# Sensor_Schematic.net
KiCad netlist of a schematic drawn in Altium Designer
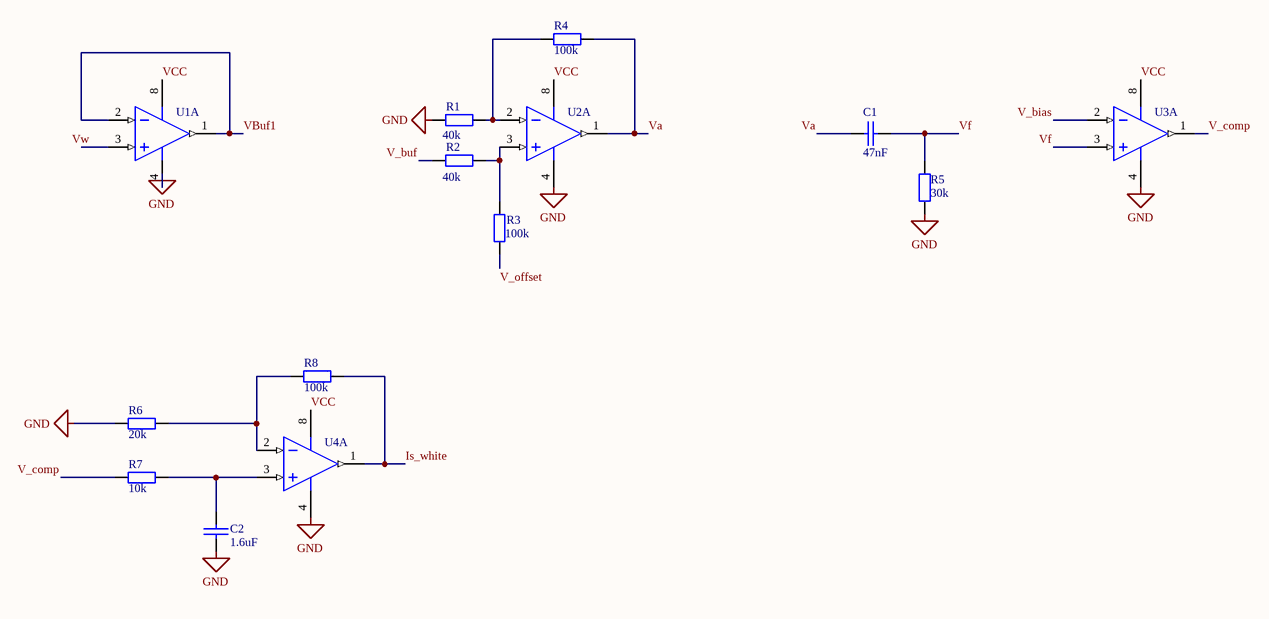
[diagram p0: Sensor Schematic.SchDoc]

(export (version "E")
  (design (tool "Eeschema 10.0.6"))
  (components
    (comp (ref "C1")
      (value "47nF")
      (footprint "0805 CAP")
      (description "SMT ceramic capacitor 0805 size")
      (libsource (lib "EE209_Library") (part "CerCap_SMT_0805"))
    )
    (comp (ref "C2")
      (value "1.6uF")
      (footprint "0805 CAP")
      (description "SMT ceramic capacitor 0805 size")
      (libsource (lib "EE209_Library") (part "CerCap_SMT_0805"))
    )
    (comp (ref "R1")
      (value "40k")
      (footprint "0805 RES")
      (description "0805 resistor")
      (fields (field (name "PUBLISHER") "Altium Limited"))
      (libsource (lib "") (part "Res_SMT_0805_1"))
    )
    (comp (ref "R2")
      (value "40k")
      (footprint "0805 RES")
      (description "0805 resistor")
      (fields (field (name "PUBLISHER") "Altium Limited"))
      (libsource (lib "") (part "Res_SMT_0805_1"))
    )
    (comp (ref "R3")
      (value "100k")
      (footprint "0805 RES")
      (description "0805 resistor")
      (fields (field (name "PUBLISHER") "Altium Limited"))
      (libsource (lib "") (part "Res_SMT_0805_2"))
    )
    (comp (ref "R4")
      (value "100k")
      (footprint "0805 RES")
      (description "0805 resistor")
      (fields (field (name "PUBLISHER") "Altium Limited"))
      (libsource (lib "EE209_Library") (part "Res_SMT_0805"))
    )
    (comp (ref "R5")
      (value "30k")
      (footprint "0805 RES")
      (description "0805 resistor")
      (fields (field (name "PUBLISHER") "Altium Limited"))
      (libsource (lib "") (part "Res_SMT_0805_2"))
    )
    (comp (ref "R6")
      (value "20k")
      (footprint "0805 RES")
      (description "0805 resistor")
      (fields (field (name "PUBLISHER") "Altium Limited"))
      (libsource (lib "EE209_Library") (part "Res_SMT_0805"))
    )
    (comp (ref "R7")
      (value "10k")
      (footprint "0805 RES")
      (description "0805 resistor")
      (fields (field (name "PUBLISHER") "Altium Limited"))
      (libsource (lib "EE209_Library") (part "Res_SMT_0805"))
    )
    (comp (ref "R8")
      (value "100k")
      (footprint "0805 RES")
      (description "0805 resistor")
      (fields (field (name "PUBLISHER") "Altium Limited"))
      (libsource (lib "EE209_Library") (part "Res_SMT_0805"))
    )
    (comp (ref "U1")
      (value "~")
      (footprint "SO - 8")
      (description "IC OPAMP GP 10MHZ 8SOIC")
      (fields
        (field (name "MANUFACTURER") "Texas Instruments")
        (field (name "MANUFACTURER PART NUMBER") "TLC082CDR")
      )
      (libsource (lib "EE209_Library") (part "TLC082_SMT_SOIC8"))
    )
    (comp (ref "U2")
      (value "~")
      (footprint "SO - 8")
      (description "IC OPAMP GP 10MHZ 8SOIC")
      (fields
        (field (name "MANUFACTURER") "Texas Instruments")
        (field (name "MANUFACTURER PART NUMBER") "TLC082CDR")
      )
      (libsource (lib "EE209_Library") (part "TLC082_SMT_SOIC8"))
    )
    (comp (ref "U3")
      (value "~")
      (footprint "SO - 8")
      (description "IC OPAMP GP 10MHZ 8SOIC")
      (fields
        (field (name "MANUFACTURER") "Texas Instruments")
        (field (name "MANUFACTURER PART NUMBER") "TLC082CDR")
      )
      (libsource (lib "EE209_Library") (part "TLC082_SMT_SOIC8"))
    )
    (comp (ref "U4")
      (value "~")
      (footprint "SO - 8")
      (description "IC OPAMP GP 10MHZ 8SOIC")
      (fields
        (field (name "MANUFACTURER") "Texas Instruments")
        (field (name "MANUFACTURER PART NUMBER") "TLC082CDR")
      )
      (libsource (lib "EE209_Library") (part "TLC082_SMT_SOIC8"))
    )
  )
  (nets
    (net (code "1") (name "/Is_white") (class "Default")
      (node (ref "R8") (pin "1") (pinfunction "1_1") (pintype "passive"))
      (node (ref "U4") (pin "1") (pinfunction "VOUTA_1") (pintype "output"))
    )
    (net (code "2") (name "/VBuf1") (class "Default")
      (node (ref "U1") (pin "1") (pinfunction "VOUTA_1") (pintype "output"))
      (node (ref "U1") (pin "2") (pinfunction "VINA-_2") (pintype "input"))
    )
    (net (code "3") (name "/VCC") (class "Default")
      (node (ref "U1") (pin "8") (pinfunction "VDD_8") (pintype "power_in"))
      (node (ref "U2") (pin "8") (pinfunction "VDD_8") (pintype "power_in"))
      (node (ref "U3") (pin "8") (pinfunction "VDD_8") (pintype "power_in"))
      (node (ref "U4") (pin "8") (pinfunction "VDD_8") (pintype "power_in"))
    )
    (net (code "4") (name "/V_bias") (class "Default")
      (node (ref "U3") (pin "2") (pinfunction "VINA-_2") (pintype "input"))
    )
    (net (code "5") (name "/V_buf") (class "Default")
      (node (ref "R2") (pin "1") (pinfunction "1_1") (pintype "passive"))
    )
    (net (code "6") (name "/V_comp") (class "Default")
      (node (ref "R7") (pin "2") (pinfunction "2_2") (pintype "passive"))
      (node (ref "U3") (pin "1") (pinfunction "VOUTA_1") (pintype "output"))
    )
    (net (code "7") (name "/V_offset") (class "Default")
      (node (ref "R3") (pin "1") (pinfunction "1_1") (pintype "passive"))
    )
    (net (code "8") (name "/Va") (class "Default")
      (node (ref "C1") (pin "1") (pinfunction "1_1") (pintype "passive"))
      (node (ref "R4") (pin "1") (pinfunction "1_1") (pintype "passive"))
      (node (ref "U2") (pin "1") (pinfunction "VOUTA_1") (pintype "output"))
    )
    (net (code "9") (name "/Vf") (class "Default")
      (node (ref "C1") (pin "2") (pinfunction "2_2") (pintype "passive"))
      (node (ref "R5") (pin "2") (pinfunction "2_2") (pintype "passive"))
      (node (ref "U3") (pin "3") (pinfunction "VINA+_3") (pintype "input"))
    )
    (net (code "10") (name "/Vw") (class "Default")
      (node (ref "U1") (pin "3") (pinfunction "VINA+_3") (pintype "input"))
    )
    (net (code "11") (name "GND") (class "Default")
      (node (ref "C2") (pin "1") (pinfunction "1_1") (pintype "passive"))
      (node (ref "R1") (pin "1") (pinfunction "1_1") (pintype "passive"))
      (node (ref "R5") (pin "1") (pinfunction "1_1") (pintype "passive"))
      (node (ref "R6") (pin "2") (pinfunction "2_2") (pintype "passive"))
      (node (ref "U1") (pin "4") (pinfunction "VSS_4") (pintype "power_in"))
      (node (ref "U2") (pin "4") (pinfunction "VSS_4") (pintype "power_in"))
      (node (ref "U3") (pin "4") (pinfunction "VSS_4") (pintype "power_in"))
      (node (ref "U4") (pin "4") (pinfunction "VSS_4") (pintype "power_in"))
    )
    (net (code "12") (name "Net-(U2A-VINA+)") (class "Default")
      (node (ref "R2") (pin "2") (pinfunction "2_2") (pintype "passive"))
      (node (ref "R3") (pin "2") (pinfunction "2_2") (pintype "passive"))
      (node (ref "U2") (pin "3") (pinfunction "VINA+_3") (pintype "input"))
    )
    (net (code "13") (name "Net-(U2A-VINA-)") (class "Default")
      (node (ref "R1") (pin "2") (pinfunction "2_2") (pintype "passive"))
      (node (ref "R4") (pin "2") (pinfunction "2_2") (pintype "passive"))
      (node (ref "U2") (pin "2") (pinfunction "VINA-_2") (pintype "input"))
    )
    (net (code "14") (name "Net-(U4A-VINA+)") (class "Default")
      (node (ref "C2") (pin "2") (pinfunction "2_2") (pintype "passive"))
      (node (ref "R7") (pin "1") (pinfunction "1_1") (pintype "passive"))
      (node (ref "U4") (pin "3") (pinfunction "VINA+_3") (pintype "input"))
    )
    (net (code "15") (name "Net-(U4A-VINA-)") (class "Default")
      (node (ref "R6") (pin "1") (pinfunction "1_1") (pintype "passive"))
      (node (ref "R8") (pin "2") (pinfunction "2_2") (pintype "passive"))
      (node (ref "U4") (pin "2") (pinfunction "VINA-_2") (pintype "input"))
    )
  )
)
